# LPC55S69_MINI.net
KiCad netlist of a schematic drawn in Altium Designer
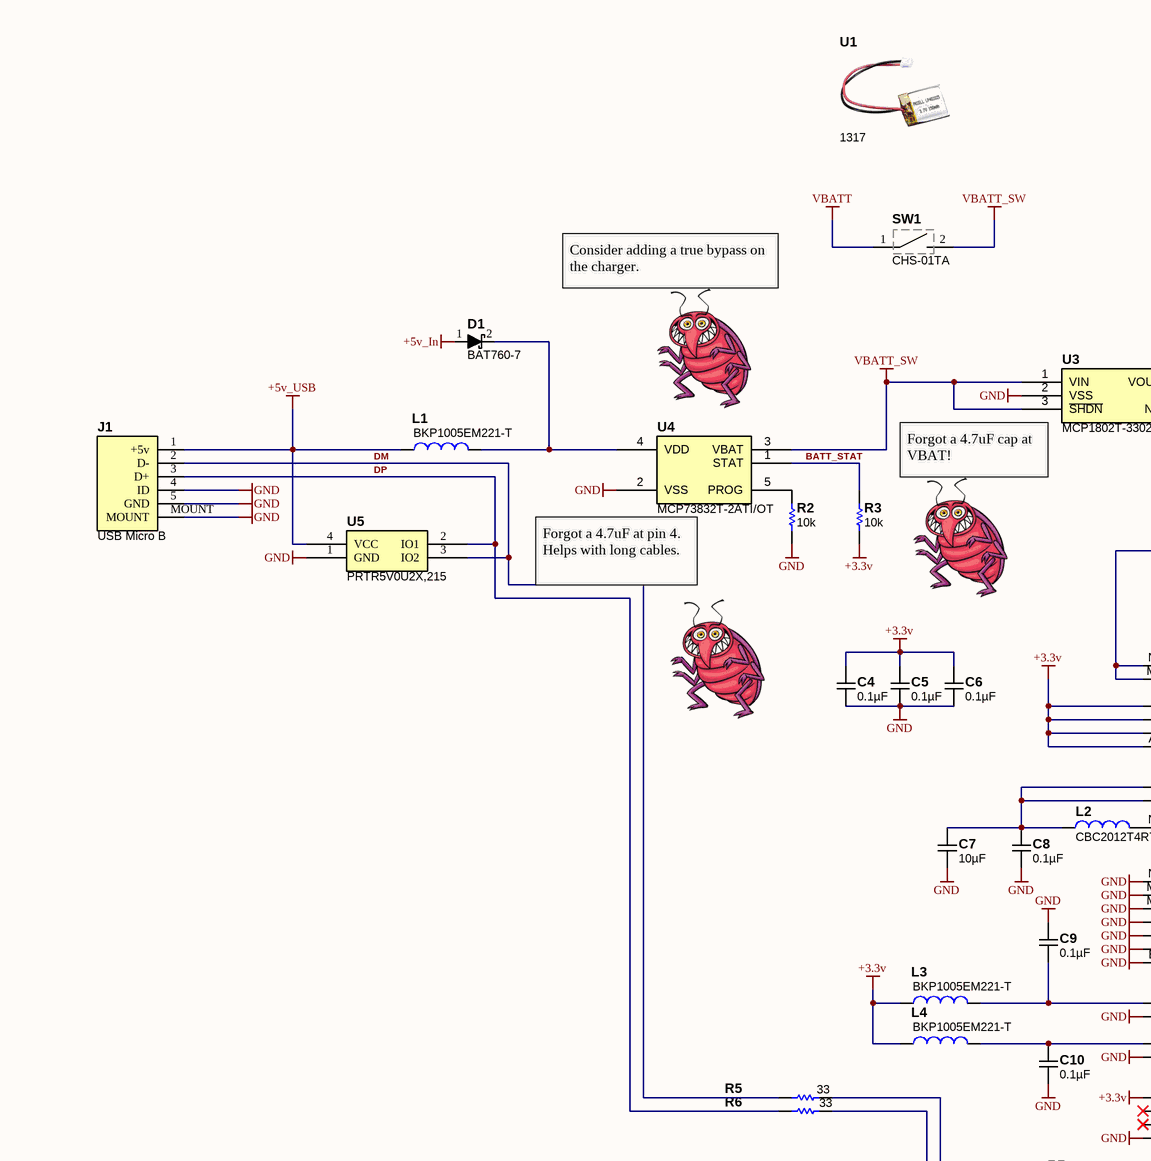
[diagram p0: LPC55S69_MINI.SchDoc, top left]
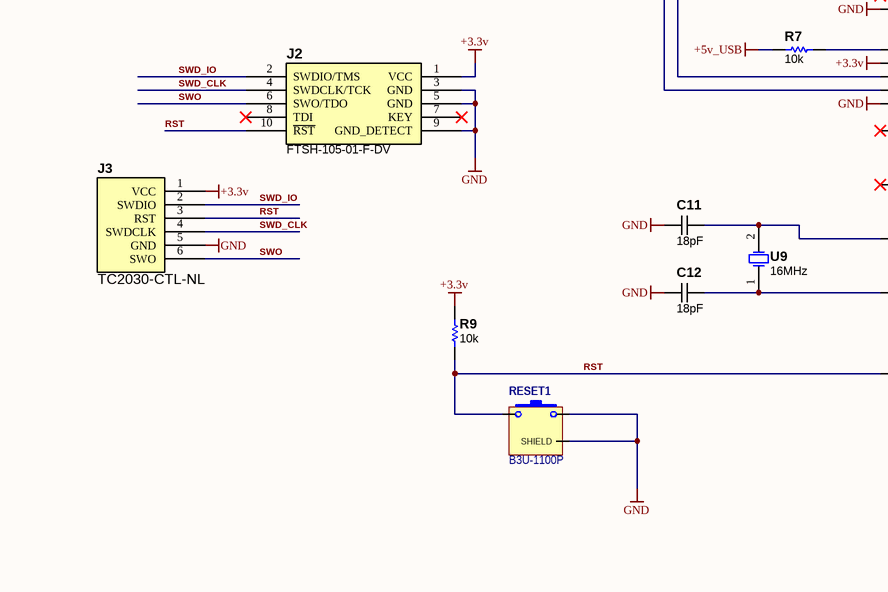
[diagram p1: LPC55S69_MINI.SchDoc, bottom left]
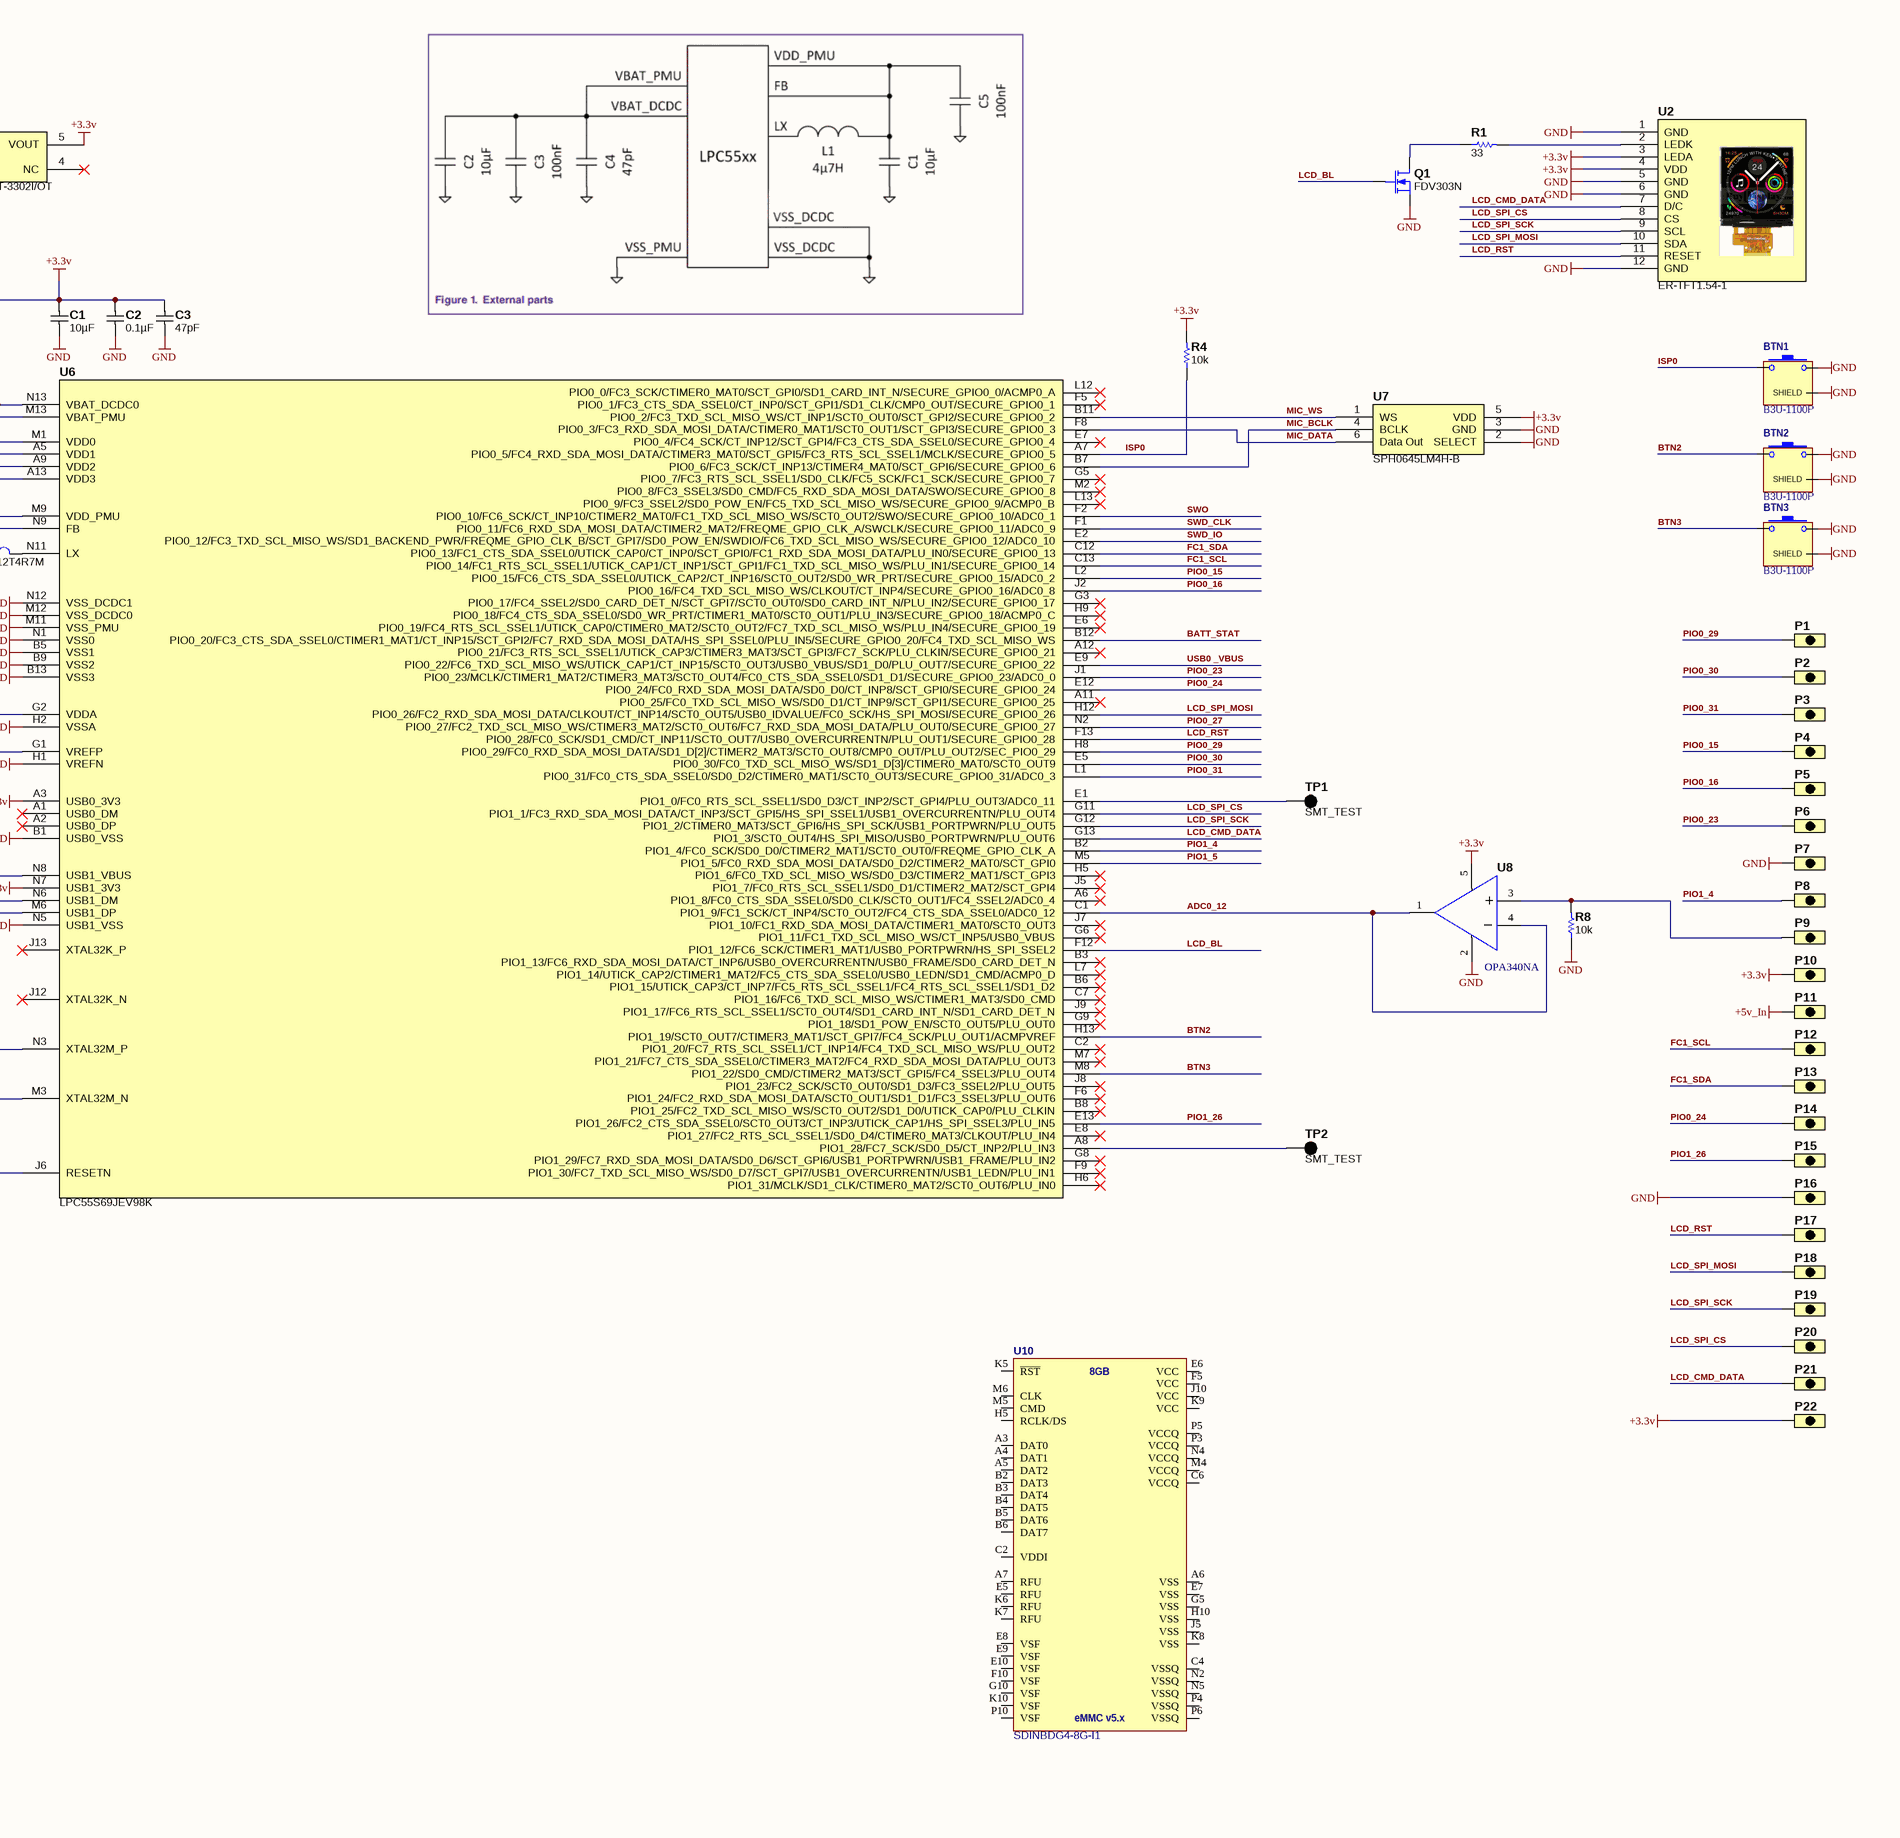
[diagram p2: LPC55S69_MINI.SchDoc, bottom right]

(export (version "E")
  (design (tool "Eeschema 10.0.6"))
  (components
    (comp (ref "BTN1")
      (value "B3U-1100P")
      (footprint "OMRON_B3U-1100P")
      (description "SWITCH TACTILE SPST-NO 0.05A 12V")
      (fields (field (name "MANUFACTURER") "Omron Electronics Inc-EMC Div"))
      (libsource (lib "Switches-N") (part "B3U-1100P"))
    )
    (comp (ref "BTN2")
      (value "B3U-1100P")
      (footprint "OMRON_B3U-1100P")
      (description "SWITCH TACTILE SPST-NO 0.05A 12V")
      (fields (field (name "MANUFACTURER") "Omron Electronics Inc-EMC Div"))
      (libsource (lib "Switches-N") (part "B3U-1100P"))
    )
    (comp (ref "BTN3")
      (value "B3U-1100P")
      (footprint "OMRON_B3U-1100P")
      (description "SWITCH TACTILE SPST-NO 0.05A 12V")
      (fields (field (name "MANUFACTURER") "Omron Electronics Inc-EMC Div"))
      (libsource (lib "Switches-N") (part "B3U-1100P"))
    )
    (comp (ref "C1")
      (value "10µF")
      (footprint "C0805_1.45MM_MD")
      (description "CAP CER 10UF 6.3V X7R 0805")
      (fields
        (field (name "MANUFACTURER PART NUMBER") "CGA4J1X7R0J106K125AC")
        (field (name "MANUFACTURER") "TDK Corporation")
      )
      (libsource (lib "Capacitors - TDK- AEC-Q200") (part "C_2P_NP"))
    )
    (comp (ref "C2")
      (value "0.1µF")
      (footprint "C0402_0.55MM_MD")
      (description "CAP CER 0.1UF 16V X7R 0402")
      (fields
        (field (name "MANUFACTURER PART NUMBER") "CGA2B1X7R1C104K050BC")
        (field (name "MANUFACTURER") "TDK Corporation")
      )
      (libsource (lib "Capacitors - TDK- AEC-Q200") (part "C_2P_NP"))
    )
    (comp (ref "C3")
      (value "47pF")
      (footprint "C0402_0.55MM_MD")
      (description "CAP CER 47PF 50V C0G 0402")
      (fields
        (field (name "MANUFACTURER PART NUMBER") "CGA2B2C0G1H470J050BA")
        (field (name "MANUFACTURER") "TDK Corporation")
      )
      (libsource (lib "Capacitors - TDK- AEC-Q200") (part "C_2P_NP"))
    )
    (comp (ref "C4")
      (value "0.1µF")
      (footprint "C0402_0.55MM_MD")
      (description "CAP CER 0.1UF 16V X7R 0402")
      (fields
        (field (name "MANUFACTURER PART NUMBER") "CGA2B1X7R1C104K050BC")
        (field (name "MANUFACTURER") "TDK Corporation")
      )
      (libsource (lib "Capacitors - TDK- AEC-Q200") (part "C_2P_NP"))
    )
    (comp (ref "C5")
      (value "0.1µF")
      (footprint "C0402_0.55MM_MD")
      (description "CAP CER 0.1UF 16V X7R 0402")
      (fields
        (field (name "MANUFACTURER PART NUMBER") "CGA2B1X7R1C104K050BC")
        (field (name "MANUFACTURER") "TDK Corporation")
      )
      (libsource (lib "Capacitors - TDK- AEC-Q200") (part "C_2P_NP"))
    )
    (comp (ref "C6")
      (value "0.1µF")
      (footprint "C0402_0.55MM_MD")
      (description "CAP CER 0.1UF 16V X7R 0402")
      (fields
        (field (name "MANUFACTURER PART NUMBER") "CGA2B1X7R1C104K050BC")
        (field (name "MANUFACTURER") "TDK Corporation")
      )
      (libsource (lib "Capacitors - TDK- AEC-Q200") (part "C_2P_NP"))
    )
    (comp (ref "C7")
      (value "10µF")
      (footprint "C0805_1.45MM_MD")
      (description "CAP CER 10UF 6.3V X7R 0805")
      (fields
        (field (name "MANUFACTURER PART NUMBER") "CGA4J1X7R0J106K125AC")
        (field (name "MANUFACTURER") "TDK Corporation")
      )
      (libsource (lib "Capacitors - TDK- AEC-Q200") (part "C_2P_NP"))
    )
    (comp (ref "C8")
      (value "0.1µF")
      (footprint "C0402_0.55MM_MD")
      (description "CAP CER 0.1UF 16V X7R 0402")
      (fields
        (field (name "MANUFACTURER PART NUMBER") "CGA2B1X7R1C104K050BC")
        (field (name "MANUFACTURER") "TDK Corporation")
      )
      (libsource (lib "Capacitors - TDK- AEC-Q200") (part "C_2P_NP"))
    )
    (comp (ref "C9")
      (value "0.1µF")
      (footprint "C0402_0.55MM_MD")
      (description "CAP CER 0.1UF 16V X7R 0402")
      (fields
        (field (name "MANUFACTURER PART NUMBER") "CGA2B1X7R1C104K050BC")
        (field (name "MANUFACTURER") "TDK Corporation")
      )
      (libsource (lib "Capacitors - TDK- AEC-Q200") (part "C_2P_NP"))
    )
    (comp (ref "C10")
      (value "0.1µF")
      (footprint "C0402_0.55MM_MD")
      (description "CAP CER 0.1UF 16V X7R 0402")
      (fields
        (field (name "MANUFACTURER PART NUMBER") "CGA2B1X7R1C104K050BC")
        (field (name "MANUFACTURER") "TDK Corporation")
      )
      (libsource (lib "Capacitors - TDK- AEC-Q200") (part "C_2P_NP"))
    )
    (comp (ref "C11")
      (value "18pF")
      (footprint "C0402_0.55MM_MD")
      (description "CAP CER 18PF 50V C0G 0402")
      (fields
        (field (name "MANUFACTURER PART NUMBER") "CGA2B2C0G1H180J050BA")
        (field (name "MANUFACTURER") "TDK Corporation")
      )
      (libsource (lib "Capacitors - TDK- AEC-Q200") (part "C_2P_NP"))
    )
    (comp (ref "C12")
      (value "18pF")
      (footprint "C0402_0.55MM_MD")
      (description "CAP CER 18PF 50V C0G 0402")
      (fields
        (field (name "MANUFACTURER PART NUMBER") "CGA2B2C0G1H180J050BA")
        (field (name "MANUFACTURER") "TDK Corporation")
      )
      (libsource (lib "Capacitors - TDK- AEC-Q200") (part "C_2P_NP"))
    )
    (comp (ref "D1")
      (value "BAT760-7")
      (footprint "D_SOD-323_P")
      (description "DIODE SCHOTTKY 30V 1A SOD323")
      (fields (field (name "MANUFACTURER") "Diodes Inc"))
      (libsource (lib "Diodes") (part "DS_1A_2C"))
    )
    (comp (ref "J1")
      (value "USB Micro B")
      (footprint "10103594-0001LF - No Slots")
      (description "CONN RCPT STD MICRO USB TYPE B")
      (fields (field (name "MANUFACTURER") "FCI") (field (name "MANUFACTURER PART NUMBER") "10103594-0001LF"))
      (libsource (lib "eConnector_USB") (part "10103594-0001LF"))
    )
    (comp (ref "J2")
      (value "FTSH-105-01-F-DV")
      (footprint "FTSH-105-01-F-DV-K-A")
      (description "SAMTEC - FTSH-105-01-F-DV - .050 X .050")
      (fields (field (name "MANUFACTURER") "SAMTEC"))
      (libsource (lib "eConnector") (part "CORTEX-DEBUG"))
    )
    (comp (ref "J3")
      (value "TC2030‐CTL‐NL")
      (footprint "TC2030 NO LATCH")
      (description "Tag Connect Pads - No latching Clips - ARM")
      (libsource (lib "eConnector") (part "TC2030‐CTL‐NL"))
    )
    (comp (ref "L1")
      (value "BKP1005EM221-T")
      (footprint "C0402_HD")
      (description "FERRITE BEAD 220 OHM 0402 1LN")
      (fields (field (name "MANUFACTURER") "Taiyo Yuden"))
      (libsource (lib "eInductor") (part "BKP1005EM221-T"))
    )
    (comp (ref "L2")
      (value "CBC2012T4R7M")
      (footprint "C0805_1.45MM_MD")
      (description "FIXED IND 4.7UH 520MA 650 MOHM")
      (fields (field (name "MANUFACTURER") "Taiyo Yuden") (field (name "TOLERANCE") "20%"))
      (libsource (lib "eInductor") (part "CBC2012T4R7M"))
    )
    (comp (ref "L3")
      (value "BKP1005EM221-T")
      (footprint "C0402_HD")
      (description "FERRITE BEAD 220 OHM 0402 1LN")
      (fields (field (name "MANUFACTURER") "Taiyo Yuden"))
      (libsource (lib "eInductor") (part "BKP1005EM221-T"))
    )
    (comp (ref "L4")
      (value "BKP1005EM221-T")
      (footprint "C0402_HD")
      (description "FERRITE BEAD 220 OHM 0402 1LN")
      (fields (field (name "MANUFACTURER") "Taiyo Yuden"))
      (libsource (lib "eInductor") (part "BKP1005EM221-T"))
    )
    (comp (ref "P1")
      (value "~")
      (footprint "CASTELLATED")
      (libsource (lib "eConnector") (part "CASTELLATED"))
    )
    (comp (ref "P2")
      (value "~")
      (footprint "CASTELLATED")
      (libsource (lib "eConnector") (part "CASTELLATED"))
    )
    (comp (ref "P3")
      (value "~")
      (footprint "CASTELLATED")
      (libsource (lib "eConnector") (part "CASTELLATED"))
    )
    (comp (ref "P4")
      (value "~")
      (footprint "CASTELLATED")
      (libsource (lib "eConnector") (part "CASTELLATED"))
    )
    (comp (ref "P5")
      (value "~")
      (footprint "CASTELLATED")
      (libsource (lib "eConnector") (part "CASTELLATED"))
    )
    (comp (ref "P6")
      (value "~")
      (footprint "CASTELLATED")
      (libsource (lib "eConnector") (part "CASTELLATED"))
    )
    (comp (ref "P7")
      (value "~")
      (footprint "CASTELLATED")
      (libsource (lib "eConnector") (part "CASTELLATED"))
    )
    (comp (ref "P8")
      (value "~")
      (footprint "CASTELLATED")
      (libsource (lib "eConnector") (part "CASTELLATED"))
    )
    (comp (ref "P9")
      (value "~")
      (footprint "CASTELLATED")
      (libsource (lib "eConnector") (part "CASTELLATED"))
    )
    (comp (ref "P10")
      (value "~")
      (footprint "CASTELLATED")
      (libsource (lib "eConnector") (part "CASTELLATED"))
    )
    (comp (ref "P11")
      (value "~")
      (footprint "CASTELLATED")
      (libsource (lib "eConnector") (part "CASTELLATED"))
    )
    (comp (ref "P12")
      (value "~")
      (footprint "CASTELLATED")
      (libsource (lib "eConnector") (part "CASTELLATED"))
    )
    (comp (ref "P13")
      (value "~")
      (footprint "CASTELLATED")
      (libsource (lib "eConnector") (part "CASTELLATED"))
    )
    (comp (ref "P14")
      (value "~")
      (footprint "CASTELLATED")
      (libsource (lib "eConnector") (part "CASTELLATED"))
    )
    (comp (ref "P15")
      (value "~")
      (footprint "CASTELLATED")
      (libsource (lib "eConnector") (part "CASTELLATED"))
    )
    (comp (ref "P16")
      (value "~")
      (footprint "CASTELLATED")
      (libsource (lib "eConnector") (part "CASTELLATED"))
    )
    (comp (ref "P17")
      (value "~")
      (footprint "CASTELLATED")
      (libsource (lib "eConnector") (part "CASTELLATED"))
    )
    (comp (ref "P18")
      (value "~")
      (footprint "CASTELLATED")
      (libsource (lib "eConnector") (part "CASTELLATED"))
    )
    (comp (ref "P19")
      (value "~")
      (footprint "CASTELLATED")
      (libsource (lib "eConnector") (part "CASTELLATED"))
    )
    (comp (ref "P20")
      (value "~")
      (footprint "CASTELLATED")
      (libsource (lib "eConnector") (part "CASTELLATED"))
    )
    (comp (ref "P21")
      (value "~")
      (footprint "CASTELLATED")
      (libsource (lib "eConnector") (part "CASTELLATED"))
    )
    (comp (ref "P22")
      (value "~")
      (footprint "CASTELLATED")
      (libsource (lib "eConnector") (part "CASTELLATED"))
    )
    (comp (ref "Q1")
      (value "FDV303N")
      (footprint "SOT-23")
      (description "MOSFET N-CH 25V 680MA SOT-23")
      (fields (field (name "MANUFACTURER") "Fairchild Semiconductor") (field (name "SOURCE") "Digikey"))
      (libsource (lib "eTransistor") (part "FDV303N"))
    )
    (comp (ref "R1")
      (value "33")
      (footprint "R0603_0.55MM_MD")
      (description "RES 33 OHM 1/10W 1% 0603 SMD")
      (fields
        (field (name "MANUFACTURER PART NUMBER") "ERJ-3EKF33R0V")
        (field (name "MANUFACTURER") "Panasonic Electronic Components")
      )
      (libsource (lib "Resistors - Panasonic - AEC-Q200") (part "R_2P"))
    )
    (comp (ref "R2")
      (value "10k")
      (footprint "R0402_0.40MM_MD")
      (description "RES 10K OHM 1/10W 1% 0402 SMD")
      (fields
        (field (name "MANUFACTURER PART NUMBER") "ERJ-2RKF1002X")
        (field (name "MANUFACTURER") "Panasonic Electronic Components")
      )
      (libsource (lib "Resistors - Panasonic - AEC-Q200") (part "R_2P"))
    )
    (comp (ref "R3")
      (value "10k")
      (footprint "R0402_0.40MM_MD")
      (description "RES 10K OHM 1/10W 1% 0402 SMD")
      (fields
        (field (name "MANUFACTURER PART NUMBER") "ERJ-2RKF1002X")
        (field (name "MANUFACTURER") "Panasonic Electronic Components")
      )
      (libsource (lib "Resistors - Panasonic - AEC-Q200") (part "R_2P"))
    )
    (comp (ref "R4")
      (value "10k")
      (footprint "R0402_0.40MM_MD")
      (description "RES 10K OHM 1/10W 1% 0402 SMD")
      (fields
        (field (name "MANUFACTURER PART NUMBER") "ERJ-2RKF1002X")
        (field (name "MANUFACTURER") "Panasonic Electronic Components")
      )
      (libsource (lib "Resistors - Panasonic - AEC-Q200") (part "R_2P"))
    )
    (comp (ref "R5")
      (value "33")
      (footprint "R0603_0.55MM_MD")
      (description "RES 33 OHM 1/10W 1% 0603 SMD")
      (fields
        (field (name "MANUFACTURER PART NUMBER") "ERJ-3EKF33R0V")
        (field (name "MANUFACTURER") "Panasonic Electronic Components")
      )
      (libsource (lib "Resistors - Panasonic - AEC-Q200") (part "R_2P"))
    )
    (comp (ref "R6")
      (value "33")
      (footprint "R0603_0.55MM_MD")
      (description "RES 33 OHM 1/10W 1% 0603 SMD")
      (fields
        (field (name "MANUFACTURER PART NUMBER") "ERJ-3EKF33R0V")
        (field (name "MANUFACTURER") "Panasonic Electronic Components")
      )
      (libsource (lib "Resistors - Panasonic - AEC-Q200") (part "R_2P"))
    )
    (comp (ref "R7")
      (value "10k")
      (footprint "R0402_0.40MM_MD")
      (description "RES 10K OHM 1/10W 1% 0402 SMD")
      (fields
        (field (name "MANUFACTURER PART NUMBER") "ERJ-2RKF1002X")
        (field (name "MANUFACTURER") "Panasonic Electronic Components")
      )
      (libsource (lib "Resistors - Panasonic - AEC-Q200") (part "R_2P"))
    )
    (comp (ref "R8")
      (value "10k")
      (footprint "R0402_0.40MM_MD")
      (description "RES 10K OHM 1/10W 1% 0402 SMD")
      (fields
        (field (name "MANUFACTURER PART NUMBER") "ERJ-2RKF1002X")
        (field (name "MANUFACTURER") "Panasonic Electronic Components")
      )
      (libsource (lib "Resistors - Panasonic - AEC-Q200") (part "R_2P"))
    )
    (comp (ref "R9")
      (value "10k")
      (footprint "R0402_0.40MM_MD")
      (description "RES 10K OHM 1/10W 1% 0402 SMD")
      (fields
        (field (name "MANUFACTURER PART NUMBER") "ERJ-2RKF1002X")
        (field (name "MANUFACTURER") "Panasonic Electronic Components")
      )
      (libsource (lib "Resistors - Panasonic - AEC-Q200") (part "R_2P"))
    )
    (comp (ref "RESET1")
      (value "B3U-1100P")
      (footprint "OMRON_B3U-1100P")
      (description "SWITCH TACTILE SPST-NO 0.05A 12V")
      (fields (field (name "MANUFACTURER") "Omron Electronics Inc-EMC Div"))
      (libsource (lib "Switches-N") (part "B3U-1100P"))
    )
    (comp (ref "SW1")
      (value "CHS-01TA")
      (footprint "CHS-01TA")
      (description "NIDEC COPAL ELECTRONICS - CHS-01TA - DIP SWITCH, 1POS, SPST, SLIDE, SMD")
      (fields (field (name "MANUFACTURER") "Nidec Copal"))
      (libsource (lib "eElectroMechanical") (part "CHS-01TA"))
    )
    (comp (ref "TP1")
      (value "SMT_TEST")
      (footprint "SMT_TP - 25")
      (libsource (lib "eTestPoint") (part "SMT_TEST"))
    )
    (comp (ref "TP2")
      (value "SMT_TEST")
      (footprint "SMT_TP - 25")
      (libsource (lib "eTestPoint") (part "SMT_TEST"))
    )
    (comp (ref "U1")
      (value "1317")
      (footprint "LIPO-150MAH")
      (description "FLORA LI-PO BATTERY 3.7V 150MAH")
      (fields (field (name "MANUFACTURER") "Adafruit Industries"))
      (libsource (lib "eBattery") (part "1317"))
    )
    (comp (ref "U2")
      (value "ER-TFT1.54-1")
      (footprint "ER-TFT1.54-1")
      (description "1.54\" 240x240 IPS Display")
      (fields (field (name "MANUFACTURER") "Buy Display"))
      (libsource (lib "eDisplay") (part "ER-TFT1.54-1"))
    )
    (comp (ref "U3")
      (value "MCP1802T-3302I/OT")
      (footprint "SOT23-5")
      (description "IC REG LINEAR 3.3V 300MA SOT23-5")
      (fields (field (name "MANUFACTURER") "Microchip"))
      (libsource (lib "eIC_Regulator") (part "MCP1802T-3302I/OT"))
    )
    (comp (ref "U4")
      (value "MCP73832T-2ATI/OT")
      (footprint "SOT23-5")
      (description "Charge Controller Li-Ion/Li-Pol 15mA to 500mA 4.2V 5-Pin SOT-23 T/R")
      (fields (field (name "MANUFACTURER") "Microchip"))
      (libsource (lib "eIC") (part "MCP73832T-2ATI/OT"))
    )
    (comp (ref "U5")
      (value "PRTR5V0U2X,215")
      (footprint "SOT143B")
      (description "TVS DIODE 5.5VWM SOT143B")
      (fields (field (name "MANUFACTURER") "NXP Semiconductors"))
      (libsource (lib "eDiode") (part "PRTR5V0U2X,215"))
    )
    (comp (ref "U6")
      (value "LPC55S69JEV98K")
      (footprint "98-VFBGA")
      (description "IC MCU 100MHZ CORTEX M33 DUAL")
      (fields (field (name "MANUFACTURER") "NXP Semiconductors"))
      (libsource (lib "eIC") (part "LPC55S69JEV98K"))
    )
    (comp (ref "U7")
      (value "SPH0645LM4H-B")
      (footprint "SPH0645LM4H-B")
      (fields (field (name "MANUFACTURER") "Knowles Acoustics"))
      (libsource (lib "eAudio") (part "SPH0645LM4H-B"))
    )
    (comp (ref "U8")
      (value "OPA340NA")
      (footprint "SOT95P245X145-5L")
      (description "IC SINGLE SUPPLY OPAMP SOT-23-5")
      (fields
        (field (name "MANUFACTURER") "Texas Instruments")
        (field (name "MANUFACTURER PART NUMBER") "OPA340NA/250")
        (field (name "SOURCE") "Digikey")
      )
      (libsource (lib "eOPAMP") (part "OPA340"))
    )
    (comp (ref "U9")
      (value "16MHz")
      (footprint "ABM3")
      (description "Crystal 16MHz ±20ppm (Tol) ±50ppm (Stability) 18pF FUND 50Ohm 2-Pin CSMD T/R")
      (fields
        (field (name "MANUFACTURER") "Abracon")
        (field (name "MANUFACTURER PART NUMBER") "ABM3-16.000MHZ-B2-T")
      )
      (libsource (lib "eCrystal") (part "ABM3-16.000MHZ-B2-T"))
    )
    (comp (ref "U10")
      (value "SDINBDG4-8G-I1")
      (footprint "BGA_JDEC_EMMC_11.5x13.1x1.1_153PIN")
      (description "eMMC eMMC seq 300/40 IOPs 7800/8000")
      (fields (field (name "MANUFACTURER") "SanDisk"))
      (libsource (lib "Memory-N") (part "SDINBDG4-8G-I1"))
    )
  )
  (nets
    (net (code "1") (name "+3.3v") (class "Default")
      (node (ref "C1") (pin "2") (pinfunction "1_2") (pintype "passive"))
      (node (ref "C2") (pin "2") (pinfunction "1_2") (pintype "passive"))
      (node (ref "C3") (pin "2") (pinfunction "1_2") (pintype "passive"))
      (node (ref "C4") (pin "2") (pinfunction "1_2") (pintype "passive"))
      (node (ref "C5") (pin "2") (pinfunction "1_2") (pintype "passive"))
      (node (ref "C6") (pin "2") (pinfunction "1_2") (pintype "passive"))
      (node (ref "J2") (pin "1") (pinfunction "VCC_1") (pintype "passive"))
      (node (ref "J3") (pin "1") (pinfunction "VCC_1") (pintype "passive"))
      (node (ref "L3") (pin "1") (pinfunction "1_1") (pintype "passive"))
      (node (ref "L4") (pin "1") (pinfunction "1_1") (pintype "passive"))
      (node (ref "P10") (pin "1") (pinfunction "1_1") (pintype "passive"))
      (node (ref "P22") (pin "1") (pinfunction "1_1") (pintype "passive"))
      (node (ref "R3") (pin "1") (pinfunction "1_1") (pintype "passive"))
      (node (ref "R4") (pin "2") (pinfunction "2_2") (pintype "passive"))
      (node (ref "R9") (pin "2") (pinfunction "2_2") (pintype "passive"))
      (node (ref "U2") (pin "3") (pinfunction "LEDA_3") (pintype "passive"))
      (node (ref "U2") (pin "4") (pinfunction "VDD_4") (pintype "passive"))
      (node (ref "U3") (pin "5") (pinfunction "VOUT_5") (pintype "passive"))
      (node (ref "U6") (pin "A13") (pinfunction "VDD3_A13") (pintype "passive"))
      (node (ref "U6") (pin "A3") (pinfunction "USB0_3V3_A3") (pintype "passive"))
      (node (ref "U6") (pin "A5") (pinfunction "VDD1_A5") (pintype "passive"))
      (node (ref "U6") (pin "A9") (pinfunction "VDD2_A9") (pintype "passive"))
      (node (ref "U6") (pin "M1") (pinfunction "VDD0_M1") (pintype "passive"))
      (node (ref "U6") (pin "M13") (pinfunction "VBAT_PMU_M13") (pintype "passive"))
      (node (ref "U6") (pin "N13") (pinfunction "VBAT_DCDC0_N13") (pintype "passive"))
      (node (ref "U6") (pin "N7") (pinfunction "USB1_3V3_N7") (pintype "passive"))
      (node (ref "U7") (pin "5") (pinfunction "VDD_5") (pintype "passive"))
      (node (ref "U8") (pin "5") (pinfunction "VCC_5") (pintype "passive"))
    )
    (net (code "2") (name "+5v_In") (class "Default")
      (node (ref "D1") (pin "1") (pinfunction "A_1") (pintype "passive"))
      (node (ref "P11") (pin "1") (pinfunction "1_1") (pintype "passive"))
    )
    (net (code "3") (name "+5v_USB") (class "Default")
      (node (ref "J1") (pin "1") (pinfunction "+5v_1") (pintype "passive"))
      (node (ref "L1") (pin "1") (pinfunction "1_1") (pintype "passive"))
      (node (ref "R7") (pin "2") (pinfunction "2_2") (pintype "passive"))
      (node (ref "U5") (pin "4") (pinfunction "VCC_4") (pintype "passive"))
    )
    (net (code "4") (name "/ADC0_12") (class "Default")
      (node (ref "U6") (pin "C1") (pinfunction "PIO1_9/FC1_SCK/CT_INP4/SCT0_OUT2/FC4_CTS_SDA_SSEL0/ADC0_12_C1") (pintype "passive"))
      (node (ref "U8") (pin "1") (pinfunction "OUT_1") (pintype "passive"))
      (node (ref "U8") (pin "4") (pinfunction "-_4") (pintype "passive"))
    )
    (net (code "5") (name "/BATT_STAT") (class "Default")
      (node (ref "R3") (pin "2") (pinfunction "2_2") (pintype "passive"))
      (node (ref "U4") (pin "1") (pinfunction "STAT_1") (pintype "passive"))
      (node (ref "U6") (pin "B12") (pinfunction "PIO0_20/FC3_CTS_SDA_SSEL0/CTIMER1_MAT1/CT_INP15/SCT_GPI2/FC7_RXD_SDA_MOSI_DATA/HS_SPI_SSEL0/PLU_IN5/SECURE_GPIO0_20/FC4_TXD_SCL_MISO_WS_B12") (pintype "passive"))
    )
    (net (code "6") (name "/BTN2") (class "Default")
      (node (ref "BTN2") (pin "2") (pinfunction "2_2") (pintype "passive"))
      (node (ref "U6") (pin "H13") (pinfunction "PIO1_19/SCT0_OUT7/CTIMER3_MAT1/SCT_GPI7/FC4_SCK/PLU_OUT1/ACMPVREF_H13") (pintype "passive"))
    )
    (net (code "7") (name "/BTN3") (class "Default")
      (node (ref "BTN3") (pin "2") (pinfunction "2_2") (pintype "passive"))
      (node (ref "U6") (pin "M8") (pinfunction "PIO1_22/SD0_CMD/CTIMER2_MAT3/SCT_GPI5/FC4_SSEL3/PLU_OUT4_M8") (pintype "passive"))
    )
    (net (code "8") (name "/DM") (class "Default")
      (node (ref "J1") (pin "2") (pinfunction "D-_2") (pintype "passive"))
      (node (ref "R5") (pin "1") (pinfunction "1_1") (pintype "passive"))
      (node (ref "U5") (pin "3") (pinfunction "IO2_3") (pintype "passive"))
    )
    (net (code "9") (name "/DP") (class "Default")
      (node (ref "J1") (pin "3") (pinfunction "D+_3") (pintype "passive"))
      (node (ref "R6") (pin "1") (pinfunction "1_1") (pintype "passive"))
      (node (ref "U5") (pin "2") (pinfunction "IO1_2") (pintype "passive"))
    )
    (net (code "10") (name "/FC1_SCL") (class "Default")
      (node (ref "P12") (pin "1") (pinfunction "1_1") (pintype "passive"))
      (node (ref "U6") (pin "C13") (pinfunction "PIO0_14/FC1_RTS_SCL_SSEL1/UTICK_CAP1/CT_INP1/SCT_GPI1/FC1_TXD_SCL_MISO_WS/PLU_IN1/SECURE_GPIO0_14_C13") (pintype "passive"))
    )
    (net (code "11") (name "/FC1_SDA") (class "Default")
      (node (ref "P13") (pin "1") (pinfunction "1_1") (pintype "passive"))
      (node (ref "U6") (pin "C12") (pinfunction "PIO0_13/FC1_CTS_SDA_SSEL0/UTICK_CAP0/CT_INP0/SCT_GPI0/FC1_RXD_SDA_MOSI_DATA/PLU_IN0/SECURE_GPIO0_13_C12") (pintype "passive"))
    )
    (net (code "12") (name "/ISP0") (class "Default")
      (node (ref "BTN1") (pin "2") (pinfunction "2_2") (pintype "passive"))
      (node (ref "R4") (pin "1") (pinfunction "1_1") (pintype "passive"))
      (node (ref "U6") (pin "A7") (pinfunction "PIO0_5/FC4_RXD_SDA_MOSI_DATA/CTIMER3_MAT0/SCT_GPI5/FC3_RTS_SCL_SSEL1/MCLK/SECURE_GPIO0_5_A7") (pintype "passive"))
    )
    (net (code "13") (name "/LCD_BL") (class "Default")
      (node (ref "Q1") (pin "1") (pinfunction "G_1") (pintype "passive"))
      (node (ref "U6") (pin "F12") (pinfunction "PIO1_12/FC6_SCK/CTIMER1_MAT1/USB0_PORTPWRN/HS_SPI_SSEL2_F12") (pintype "passive"))
    )
    (net (code "14") (name "/LCD_CMD_DATA") (class "Default")
      (node (ref "P21") (pin "1") (pinfunction "1_1") (pintype "passive"))
      (node (ref "U2") (pin "7") (pinfunction "D/C_7") (pintype "passive"))
      (node (ref "U6") (pin "G13") (pinfunction "PIO1_3/SCT0_OUT4/HS_SPI_MISO/USB0_PORTPWRN/PLU_OUT6_G13") (pintype "passive"))
    )
    (net (code "15") (name "/LCD_RST") (class "Default")
      (node (ref "P17") (pin "1") (pinfunction "1_1") (pintype "passive"))
      (node (ref "U2") (pin "11") (pinfunction "RESET_11") (pintype "passive"))
      (node (ref "U6") (pin "F13") (pinfunction "PIO0_28/FC0_SCK/SD1_CMD/CT_INP11/SCT0_OUT7/USB0_OVERCURRENTN/PLU_OUT1/SECURE_GPIO0_28_F13") (pintype "passive"))
    )
    (net (code "16") (name "/LCD_SPI_CS") (class "Default")
      (node (ref "P20") (pin "1") (pinfunction "1_1") (pintype "passive"))
      (node (ref "U2") (pin "8") (pinfunction "CS_8") (pintype "passive"))
      (node (ref "U6") (pin "G11") (pinfunction "PIO1_1/FC3_RXD_SDA_MOSI_DATA/CT_INP3/SCT_GPI5/HS_SPI_SSEL1/USB1_OVERCURRENTN/PLU_OUT4_G11") (pintype "passive"))
    )
    (net (code "17") (name "/LCD_SPI_MOSI") (class "Default")
      (node (ref "P18") (pin "1") (pinfunction "1_1") (pintype "passive"))
      (node (ref "U2") (pin "10") (pinfunction "SDA_10") (pintype "passive"))
      (node (ref "U6") (pin "H12") (pinfunction "PIO0_26/FC2_RXD_SDA_MOSI_DATA/CLKOUT/CT_INP14/SCT0_OUT5/USB0_IDVALUE/FC0_SCK/HS_SPI_MOSI/SECURE_GPIO0_26_H12") (pintype "passive"))
    )
    (net (code "18") (name "/LCD_SPI_SCK") (class "Default")
      (node (ref "P19") (pin "1") (pinfunction "1_1") (pintype "passive"))
      (node (ref "U2") (pin "9") (pinfunction "SCL_9") (pintype "passive"))
      (node (ref "U6") (pin "G12") (pinfunction "PIO1_2/CTIMER0_MAT3/SCT_GPI6/HS_SPI_SCK/USB1_PORTPWRN/PLU_OUT5_G12") (pintype "passive"))
    )
    (net (code "19") (name "/MIC_BCLK") (class "Default")
      (node (ref "U6") (pin "B7") (pinfunction "PIO0_6/FC3_SCK/CT_INP13/CTIMER4_MAT0/SCT_GPI6/SECURE_GPIO0_6_B7") (pintype "passive"))
      (node (ref "U7") (pin "4") (pinfunction "BCLK_4") (pintype "passive"))
    )
    (net (code "20") (name "/MIC_DATA") (class "Default")
      (node (ref "U6") (pin "F8") (pinfunction "PIO0_3/FC3_RXD_SDA_MOSI_DATA/CTIMER0_MAT1/SCT0_OUT1/SCT_GPI3/SECURE_GPIO0_3_F8") (pintype "passive"))
      (node (ref "U7") (pin "6") (pinfunction "Data_Out_6") (pintype "passive"))
    )
    (net (code "21") (name "/MIC_WS") (class "Default")
      (node (ref "U6") (pin "B11") (pinfunction "PIO0_2/FC3_TXD_SCL_MISO_WS/CT_INP1/SCT0_OUT0/SCT_GPI2/SECURE_GPIO0_2_B11") (pintype "passive"))
      (node (ref "U7") (pin "1") (pinfunction "WS_1") (pintype "passive"))
    )
    (net (code "22") (name "/PIO0_15") (class "Default")
      (node (ref "P4") (pin "1") (pinfunction "1_1") (pintype "passive"))
      (node (ref "U6") (pin "L2") (pinfunction "PIO0_15/FC6_CTS_SDA_SSEL0/UTICK_CAP2/CT_INP16/SCT0_OUT2/SD0_WR_PRT/SECURE_GPIO0_15/ADC0_2_L2") (pintype "passive"))
    )
    (net (code "23") (name "/PIO0_16") (class "Default")
      (node (ref "P5") (pin "1") (pinfunction "1_1") (pintype "passive"))
      (node (ref "U6") (pin "J2") (pinfunction "PIO0_16/FC4_TXD_SCL_MISO_WS/CLKOUT/CT_INP4/SECURE_GPIO0_16/ADC0_8_J2") (pintype "passive"))
    )
    (net (code "24") (name "/PIO0_23") (class "Default")
      (node (ref "P6") (pin "1") (pinfunction "1_1") (pintype "passive"))
      (node (ref "U6") (pin "J1") (pinfunction "PIO0_23/MCLK/CTIMER1_MAT2/CTIMER3_MAT3/SCT0_OUT4/FC0_CTS_SDA_SSEL0/SD1_D1/SECURE_GPIO0_23/ADC0_0_J1") (pintype "passive"))
    )
    (net (code "25") (name "/PIO0_24") (class "Default")
      (node (ref "P14") (pin "1") (pinfunction "1_1") (pintype "passive"))
      (node (ref "U6") (pin "E12") (pinfunction "PIO0_24/FC0_RXD_SDA_MOSI_DATA/SD0_D0/CT_INP8/SCT_GPI0/SECURE_GPIO0_24_E12") (pintype "passive"))
    )
    (net (code "26") (name "/PIO0_27") (class "Default")
      (node (ref "U6") (pin "N2") (pinfunction "PIO0_27/FC2_TXD_SCL_MISO_WS/CTIMER3_MAT2/SCT0_OUT6/FC7_RXD_SDA_MOSI_DATA/PLU_OUT0/SECURE_GPIO0_27_N2") (pintype "passive"))
    )
    (net (code "27") (name "/PIO0_29") (class "Default")
      (node (ref "P1") (pin "1") (pinfunction "1_1") (pintype "passive"))
      (node (ref "U6") (pin "H8") (pinfunction "PIO0_29/FC0_RXD_SDA_MOSI_DATA/SD1_D[2]/CTIMER2_MAT3/SCT0_OUT8/CMP0_OUT/PLU_OUT2/SEC_PIO0_29_H8") (pintype "passive"))
    )
    (net (code "28") (name "/PIO0_30") (class "Default")
      (node (ref "P2") (pin "1") (pinfunction "1_1") (pintype "passive"))
      (node (ref "U6") (pin "E5") (pinfunction "PIO0_30/FC0_TXD_SCL_MISO_WS/SD1_D[3]/CTIMER0_MAT0/SCT0_OUT9_E5") (pintype "passive"))
    )
    (net (code "29") (name "/PIO0_31") (class "Default")
      (node (ref "P3") (pin "1") (pinfunction "1_1") (pintype "passive"))
      (node (ref "U6") (pin "L1") (pinfunction "PIO0_31/FC0_CTS_SDA_SSEL0/SD0_D2/CTIMER0_MAT1/SCT0_OUT3/SECURE_GPIO0_31/ADC0_3_L1") (pintype "passive"))
    )
    (net (code "30") (name "/PIO1_4") (class "Default")
      (node (ref "P8") (pin "1") (pinfunction "1_1") (pintype "passive"))
      (node (ref "U6") (pin "B2") (pinfunction "PIO1_4/FC0_SCK/SD0_D0/CTIMER2_MAT1/SCT0_OUT0/FREQME_GPIO_CLK_A_B2") (pintype "passive"))
    )
    (net (code "31") (name "/PIO1_5") (class "Default")
      (node (ref "U6") (pin "M5") (pinfunction "PIO1_5/FC0_RXD_SDA_MOSI_DATA/SD0_D2/CTIMER2_MAT0/SCT_GPI0_M5") (pintype "passive"))
    )
    (net (code "32") (name "/PIO1_26") (class "Default")
      (node (ref "P15") (pin "1") (pinfunction "1_1") (pintype "passive"))
      (node (ref "U6") (pin "E13") (pinfunction "PIO1_26/FC2_CTS_SDA_SSEL0/SCT0_OUT3/CT_INP3/UTICK_CAP1/HS_SPI_SSEL3/PLU_IN5_E13") (pintype "passive"))
    )
    (net (code "33") (name "/RST") (class "Default")
      (node (ref "J2") (pin "10") (pinfunction "~{RST}_10") (pintype "passive"))
      (node (ref "J3") (pin "3") (pinfunction "RST_3") (pintype "passive"))
      (node (ref "R9") (pin "1") (pinfunction "1_1") (pintype "passive"))
      (node (ref "RESET1") (pin "2") (pinfunction "2_2") (pintype "passive"))
      (node (ref "U6") (pin "J6") (pinfunction "RESETN_J6") (pintype "passive"))
    )
    (net (code "34") (name "/SWD_CLK") (class "Default")
      (node (ref "J2") (pin "4") (pinfunction "SWDCLK/TCK_4") (pintype "passive"))
      (node (ref "J3") (pin "4") (pinfunction "SWDCLK_4") (pintype "passive"))
      (node (ref "U6") (pin "F1") (pinfunction "PIO0_11/FC6_RXD_SDA_MOSI_DATA/CTIMER2_MAT2/FREQME_GPIO_CLK_A/SWCLK/SECURE_GPIO0_11/ADC0_9_F1") (pintype "passive"))
    )
    (net (code "35") (name "/SWD_IO") (class "Default")
      (node (ref "J2") (pin "2") (pinfunction "SWDIO/TMS_2") (pintype "passive"))
      (node (ref "J3") (pin "2") (pinfunction "SWDIO_2") (pintype "passive"))
      (node (ref "U6") (pin "E2") (pinfunction "PIO0_12/FC3_TXD_SCL_MISO_WS/SD1_BACKEND_PWR/FREQME_GPIO_CLK_B/SCT_GPI7/SD0_POW_EN/SWDIO/FC6_TXD_SCL_MISO_WS/SECURE_GPIO0_12/ADC0_10_E2") (pintype "passive"))
    )
    (net (code "36") (name "/SWO") (class "Default")
      (node (ref "J2") (pin "6") (pinfunction "SWO/TDO_6") (pintype "passive"))
      (node (ref "J3") (pin "6") (pinfunction "SWO_6") (pintype "passive"))
      (node (ref "U6") (pin "F2") (pinfunction "PIO0_10/FC6_SCK/CT_INP10/CTIMER2_MAT0/FC1_TXD_SCL_MISO_WS/SCT0_OUT2/SWO/SECURE_GPIO0_10/ADC0_1_F2") (pintype "passive"))
    )
    (net (code "37") (name "/USB0 _VBUS") (class "Default")
      (node (ref "U6") (pin "E9") (pinfunction "PIO0_22/FC6_TXD_SCL_MISO_WS/UTICK_CAP1/CT_INP15/SCT0_OUT3/USB0_VBUS/SD1_D0/PLU_OUT7/SECURE_GPIO0_22_E9") (pintype "passive"))
    )
    (net (code "38") (name "GND") (class "Default")
      (node (ref "BTN1") (pin "1") (pinfunction "1_1") (pintype "passive"))
      (node (ref "BTN1") (pin "S") (pinfunction "SHIELD_S") (pintype "passive"))
      (node (ref "BTN2") (pin "1") (pinfunction "1_1") (pintype "passive"))
      (node (ref "BTN2") (pin "S") (pinfunction "SHIELD_S") (pintype "passive"))
      (node (ref "BTN3") (pin "1") (pinfunction "1_1") (pintype "passive"))
      (node (ref "BTN3") (pin "S") (pinfunction "SHIELD_S") (pintype "passive"))
      (node (ref "C1") (pin "1") (pinfunction "1_1") (pintype "passive"))
      (node (ref "C10") (pin "1") (pinfunction "1_1") (pintype "passive"))
      (node (ref "C11") (pin "1") (pinfunction "1_1") (pintype "passive"))
      (node (ref "C12") (pin "1") (pinfunction "1_1") (pintype "passive"))
      (node (ref "C2") (pin "1") (pinfunction "1_1") (pintype "passive"))
      (node (ref "C3") (pin "1") (pinfunction "1_1") (pintype "passive"))
      (node (ref "C4") (pin "1") (pinfunction "1_1") (pintype "passive"))
      (node (ref "C5") (pin "1") (pinfunction "1_1") (pintype "passive"))
      (node (ref "C6") (pin "1") (pinfunction "1_1") (pintype "passive"))
      (node (ref "C7") (pin "1") (pinfunction "1_1") (pintype "passive"))
      (node (ref "C8") (pin "1") (pinfunction "1_1") (pintype "passive"))
      (node (ref "C9") (pin "2") (pinfunction "1_2") (pintype "passive"))
      (node (ref "J1") (pin "4") (pinfunction "ID_4") (pintype "passive"))
      (node (ref "J1") (pin "5") (pinfunction "GND_5") (pintype "passive"))
      (node (ref "J1") (pin "MOUNT") (pinfunction "MOUNT_MOUNT") (pintype "passive"))
      (node (ref "J2") (pin "3") (pinfunction "GND_3") (pintype "passive"))
      (node (ref "J2") (pin "5") (pinfunction "GND_5") (pintype "passive"))
      (node (ref "J2") (pin "9") (pinfunction "GND_DETECT_9") (pintype "passive"))
      (node (ref "J3") (pin "5") (pinfunction "GND_5") (pintype "passive"))
      (node (ref "P16") (pin "1") (pinfunction "1_1") (pintype "passive"))
      (node (ref "P7") (pin "1") (pinfunction "1_1") (pintype "passive"))
      (node (ref "Q1") (pin "2") (pinfunction "S_2") (pintype "passive"))
      (node (ref "R2") (pin "1") (pinfunction "1_1") (pintype "passive"))
      (node (ref "R8") (pin "1") (pinfunction "1_1") (pintype "passive"))
      (node (ref "RESET1") (pin "1") (pinfunction "1_1") (pintype "passive"))
      (node (ref "RESET1") (pin "S") (pinfunction "SHIELD_S") (pintype "passive"))
      (node (ref "U2") (pin "1") (pinfunction "GND_1") (pintype "passive"))
      (node (ref "U2") (pin "12") (pinfunction "GND_12") (pintype "passive"))
      (node (ref "U2") (pin "5") (pinfunction "GND_5") (pintype "passive"))
      (node (ref "U2") (pin "6") (pinfunction "GND_6") (pintype "passive"))
      (node (ref "U3") (pin "2") (pinfunction "VSS_2") (pintype "passive"))
      (node (ref "U4") (pin "2") (pinfunction "VSS_2") (pintype "passive"))
      (node (ref "U5") (pin "1") (pinfunction "GND_1") (pintype "passive"))
      (node (ref "U6") (pin "B1") (pinfunction "USB0_VSS_B1") (pintype "passive"))
      (node (ref "U6") (pin "B13") (pinfunction "VSS3_B13") (pintype "passive"))
      (node (ref "U6") (pin "B5") (pinfunction "VSS1_B5") (pintype "passive"))
      (node (ref "U6") (pin "B9") (pinfunction "VSS2_B9") (pintype "passive"))
      (node (ref "U6") (pin "H1") (pinfunction "VREFN_H1") (pintype "passive"))
      (node (ref "U6") (pin "H2") (pinfunction "VSSA_H2") (pintype "passive"))
      (node (ref "U6") (pin "M11") (pinfunction "VSS_PMU_M11") (pintype "passive"))
      (node (ref "U6") (pin "M12") (pinfunction "VSS_DCDC0_M12") (pintype "passive"))
      (node (ref "U6") (pin "N1") (pinfunction "VSS0_N1") (pintype "passive"))
      (node (ref "U6") (pin "N12") (pinfunction "VSS_DCDC1_N12") (pintype "passive"))
      (node (ref "U6") (pin "N5") (pinfunction "USB1_VSS_N5") (pintype "passive"))
      (node (ref "U7") (pin "2") (pinfunction "SELECT_2") (pintype "passive"))
      (node (ref "U7") (pin "3") (pinfunction "GND_3") (pintype "passive"))
      (node (ref "U8") (pin "2") (pinfunction "GND_2") (pintype "passive"))
    )
    (net (code "39") (name "Net-(D1-K)") (class "Default")
      (node (ref "D1") (pin "2") (pinfunction "K_2") (pintype "passive"))
      (node (ref "L1") (pin "2") (pinfunction "2_2") (pintype "passive"))
      (node (ref "U4") (pin "4") (pinfunction "VDD_4") (pintype "passive"))
    )
    (net (code "40") (name "Net-(Q1-D)") (class "Default")
      (node (ref "Q1") (pin "3") (pinfunction "D_3") (pintype "passive"))
      (node (ref "R1") (pin "1") (pinfunction "1_1") (pintype "passive"))
    )
    (net (code "41") (name "Net-(U2-LEDK)") (class "Default")
      (node (ref "R1") (pin "2") (pinfunction "2_2") (pintype "passive"))
      (node (ref "U2") (pin "2") (pinfunction "LEDK_2") (pintype "passive"))
    )
    (net (code "42") (name "Net-(U4-PROG)") (class "Default")
      (node (ref "R2") (pin "2") (pinfunction "2_2") (pintype "passive"))
      (node (ref "U4") (pin "5") (pinfunction "PROG_5") (pintype "passive"))
    )
    (net (code "43") (name "Net-(U6-FB)") (class "Default")
      (node (ref "C7") (pin "2") (pinfunction "1_2") (pintype "passive"))
      (node (ref "C8") (pin "2") (pinfunction "1_2") (pintype "passive"))
      (node (ref "L2") (pin "1") (pinfunction "1_1") (pintype "passive"))
      (node (ref "U6") (pin "M9") (pinfunction "VDD_PMU_M9") (pintype "passive"))
      (node (ref "U6") (pin "N9") (pinfunction "FB_N9") (pintype "passive"))
    )
    (net (code "44") (name "Net-(U6-LX)") (class "Default")
      (node (ref "L2") (pin "2") (pinfunction "2_2") (pintype "passive"))
      (node (ref "U6") (pin "N11") (pinfunction "LX_N11") (pintype "passive"))
    )
    (net (code "45") (name "Net-(U6-PIO1_0{slash}FC0_RTS_SCL_SSEL1{slash}SD0_D3{slash}CT_INP2{slash}SCT_GPI4{slash}PLU_OUT3{slash}ADC0_11)") (class "Default")
      (node (ref "TP1") (pin "1") (pinfunction "1_1") (pintype "passive"))
      (node (ref "U6") (pin "E1") (pinfunction "PIO1_0/FC0_RTS_SCL_SSEL1/SD0_D3/CT_INP2/SCT_GPI4/PLU_OUT3/ADC0_11_E1") (pintype "passive"))
    )
    (net (code "46") (name "Net-(U6-PIO1_28{slash}FC7_SCK{slash}SD0_D5{slash}CT_INP2{slash}PLU_IN3)") (class "Default")
      (node (ref "TP2") (pin "1") (pinfunction "1_1") (pintype "passive"))
      (node (ref "U6") (pin "A8") (pinfunction "PIO1_28/FC7_SCK/SD0_D5/CT_INP2/PLU_IN3_A8") (pintype "passive"))
    )
    (net (code "47") (name "Net-(U6-USB1_DM)") (class "Default")
      (node (ref "R5") (pin "2") (pinfunction "2_2") (pintype "passive"))
      (node (ref "U6") (pin "N6") (pinfunction "USB1_DM_N6") (pintype "passive"))
    )
    (net (code "48") (name "Net-(U6-USB1_DP)") (class "Default")
      (node (ref "R6") (pin "2") (pinfunction "2_2") (pintype "passive"))
      (node (ref "U6") (pin "M6") (pinfunction "USB1_DP_M6") (pintype "passive"))
    )
    (net (code "49") (name "Net-(U6-USB1_VBUS)") (class "Default")
      (node (ref "R7") (pin "1") (pinfunction "1_1") (pintype "passive"))
      (node (ref "U6") (pin "N8") (pinfunction "USB1_VBUS_N8") (pintype "passive"))
    )
    (net (code "50") (name "Net-(U6-VDDA)") (class "Default")
      (node (ref "C9") (pin "1") (pinfunction "1_1") (pintype "passive"))
      (node (ref "L3") (pin "2") (pinfunction "2_2") (pintype "passive"))
      (node (ref "U6") (pin "G2") (pinfunction "VDDA_G2") (pintype "passive"))
    )
    (net (code "51") (name "Net-(U6-VREFP)") (class "Default")
      (node (ref "C10") (pin "2") (pinfunction "1_2") (pintype "passive"))
      (node (ref "L4") (pin "2") (pinfunction "2_2") (pintype "passive"))
      (node (ref "U6") (pin "G1") (pinfunction "VREFP_G1") (pintype "passive"))
    )
    (net (code "52") (name "Net-(U6-XTAL32M_N)") (class "Default")
      (node (ref "C12") (pin "2") (pinfunction "1_2") (pintype "passive"))
      (node (ref "U6") (pin "M3") (pinfunction "XTAL32M_N_M3") (pintype "passive"))
      (node (ref "U9") (pin "1") (pinfunction "OSC1_1") (pintype "passive"))
    )
    (net (code "53") (name "Net-(U6-XTAL32M_P)") (class "Default")
      (node (ref "C11") (pin "2") (pinfunction "1_2") (pintype "passive"))
      (node (ref "U6") (pin "N3") (pinfunction "XTAL32M_P_N3") (pintype "passive"))
      (node (ref "U9") (pin "2") (pinfunction "OSC2_2") (pintype "passive"))
    )
    (net (code "54") (name "Net-(U8-+)") (class "Default")
      (node (ref "P9") (pin "1") (pinfunction "1_1") (pintype "passive"))
      (node (ref "R8") (pin "2") (pinfunction "2_2") (pintype "passive"))
      (node (ref "U8") (pin "3") (pinfunction "+_3") (pintype "passive"))
    )
    (net (code "55") (name "VBATT") (class "Default")
      (node (ref "SW1") (pin "1") (pinfunction "1_1") (pintype "passive"))
    )
    (net (code "56") (name "VBATT_SW") (class "Default")
      (node (ref "SW1") (pin "2") (pinfunction "2_2") (pintype "passive"))
      (node (ref "U3") (pin "1") (pinfunction "VIN_1") (pintype "passive"))
      (node (ref "U3") (pin "3") (pinfunction "~{SHDN}_3") (pintype "passive"))
      (node (ref "U4") (pin "3") (pinfunction "VBAT_3") (pintype "passive"))
    )
    (net (code "57") (name "unconnected-(J2-KEY-Pad7)") (class "Default")
      (node (ref "J2") (pin "7") (pinfunction "KEY_7") (pintype "passive+no_connect"))
    )
    (net (code "58") (name "unconnected-(J2-TDI-Pad8)") (class "Default")
      (node (ref "J2") (pin "8") (pinfunction "TDI_8") (pintype "passive+no_connect"))
    )
    (net (code "59") (name "unconnected-(U3-NC-Pad4)") (class "Default")
      (node (ref "U3") (pin "4") (pinfunction "NC_4") (pintype "passive+no_connect"))
    )
    (net (code "60") (name "unconnected-(U6-PIO0_0{slash}FC3_SCK{slash}CTIMER0_MAT0{slash}SCT_GPI0{slash}SD1_CARD_INT_N{slash}SECURE_GPIO0_0{slash}ACMP0_A-PadL12)") (class "Default")
      (node (ref "U6") (pin "L12") (pinfunction "PIO0_0/FC3_SCK/CTIMER0_MAT0/SCT_GPI0/SD1_CARD_INT_N/SECURE_GPIO0_0/ACMP0_A_L12") (pintype "passive+no_connect"))
    )
    (net (code "61") (name "unconnected-(U6-PIO0_1{slash}FC3_CTS_SDA_SSEL0{slash}CT_INP0{slash}SCT_GPI1{slash}SD1_CLK{slash}CMP0_OUT{slash}SECURE_GPIO0_1-PadF5)") (class "Default")
      (node (ref "U6") (pin "F5") (pinfunction "PIO0_1/FC3_CTS_SDA_SSEL0/CT_INP0/SCT_GPI1/SD1_CLK/CMP0_OUT/SECURE_GPIO0_1_F5") (pintype "passive+no_connect"))
    )
    (net (code "62") (name "unconnected-(U6-PIO0_4{slash}FC4_SCK{slash}CT_INP12{slash}SCT_GPI4{slash}FC3_CTS_SDA_SSEL0{slash}SECURE_GPIO0_4-PadE7)") (class "Default")
      (node (ref "U6") (pin "E7") (pinfunction "PIO0_4/FC4_SCK/CT_INP12/SCT_GPI4/FC3_CTS_SDA_SSEL0/SECURE_GPIO0_4_E7") (pintype "passive+no_connect"))
    )
    (net (code "63") (name "unconnected-(U6-PIO0_7{slash}FC3_RTS_SCL_SSEL1{slash}SD0_CLK{slash}FC5_SCK{slash}FC1_SCK{slash}SECURE_GPIO0_7-PadG5)") (class "Default")
      (node (ref "U6") (pin "G5") (pinfunction "PIO0_7/FC3_RTS_SCL_SSEL1/SD0_CLK/FC5_SCK/FC1_SCK/SECURE_GPIO0_7_G5") (pintype "passive+no_connect"))
    )
    (net (code "64") (name "unconnected-(U6-PIO0_8{slash}FC3_SSEL3{slash}SD0_CMD{slash}FC5_RXD_SDA_MOSI_DATA{slash}SWO{slash}SECURE_GPIO0_8-PadM2)") (class "Default")
      (node (ref "U6") (pin "M2") (pinfunction "PIO0_8/FC3_SSEL3/SD0_CMD/FC5_RXD_SDA_MOSI_DATA/SWO/SECURE_GPIO0_8_M2") (pintype "passive+no_connect"))
    )
    (net (code "65") (name "unconnected-(U6-PIO0_9{slash}FC3_SSEL2{slash}SD0_POW_EN{slash}FC5_TXD_SCL_MISO_WS{slash}SECURE_GPIO0_9{slash}ACMP0_B-PadL13)") (class "Default")
      (node (ref "U6") (pin "L13") (pinfunction "PIO0_9/FC3_SSEL2/SD0_POW_EN/FC5_TXD_SCL_MISO_WS/SECURE_GPIO0_9/ACMP0_B_L13") (pintype "passive+no_connect"))
    )
    (net (code "66") (name "unconnected-(U6-PIO0_17{slash}FC4_SSEL2{slash}SD0_CARD_DET_N{slash}SCT_GPI7{slash}SCT0_OUT0{slash}SD0_CARD_INT_N{slash}PLU_IN2{slash}SECURE_GPIO0_17-PadG3)") (class "Default")
      (node (ref "U6") (pin "G3") (pinfunction "PIO0_17/FC4_SSEL2/SD0_CARD_DET_N/SCT_GPI7/SCT0_OUT0/SD0_CARD_INT_N/PLU_IN2/SECURE_GPIO0_17_G3") (pintype "passive+no_connect"))
    )
    (net (code "67") (name "unconnected-(U6-PIO0_18{slash}FC4_CTS_SDA_SSEL0{slash}SD0_WR_PRT{slash}CTIMER1_MAT0{slash}SCT0_OUT1{slash}PLU_IN3{slash}SECURE_GPIO0_18{slash}ACMP0_C-PadH9)") (class "Default")
      (node (ref "U6") (pin "H9") (pinfunction "PIO0_18/FC4_CTS_SDA_SSEL0/SD0_WR_PRT/CTIMER1_MAT0/SCT0_OUT1/PLU_IN3/SECURE_GPIO0_18/ACMP0_C_H9") (pintype "passive+no_connect"))
    )
    (net (code "68") (name "unconnected-(U6-PIO0_19{slash}FC4_RTS_SCL_SSEL1{slash}UTICK_CAP0{slash}CTIMER0_MAT2{slash}SCT0_OUT2{slash}FC7_TXD_SCL_MISO_WS{slash}PLU_IN4{slash}SECURE_GPIO0_19-PadE6)") (class "Default")
      (node (ref "U6") (pin "E6") (pinfunction "PIO0_19/FC4_RTS_SCL_SSEL1/UTICK_CAP0/CTIMER0_MAT2/SCT0_OUT2/FC7_TXD_SCL_MISO_WS/PLU_IN4/SECURE_GPIO0_19_E6") (pintype "passive+no_connect"))
    )
    (net (code "69") (name "unconnected-(U6-PIO0_21{slash}FC3_RTS_SCL_SSEL1{slash}UTICK_CAP3{slash}CTIMER3_MAT3{slash}SCT_GPI3{slash}FC7_SCK{slash}PLU_CLKIN{slash}SECURE_GPIO0_21-PadA12)") (class "Default")
      (node (ref "U6") (pin "A12") (pinfunction "PIO0_21/FC3_RTS_SCL_SSEL1/UTICK_CAP3/CTIMER3_MAT3/SCT_GPI3/FC7_SCK/PLU_CLKIN/SECURE_GPIO0_21_A12") (pintype "passive+no_connect"))
    )
    (net (code "70") (name "unconnected-(U6-PIO0_25{slash}FC0_TXD_SCL_MISO_WS{slash}SD0_D1{slash}CT_INP9{slash}SCT_GPI1{slash}SECURE_GPIO0_25-PadA11)") (class "Default")
      (node (ref "U6") (pin "A11") (pinfunction "PIO0_25/FC0_TXD_SCL_MISO_WS/SD0_D1/CT_INP9/SCT_GPI1/SECURE_GPIO0_25_A11") (pintype "passive+no_connect"))
    )
    (net (code "71") (name "unconnected-(U6-PIO1_6{slash}FC0_TXD_SCL_MISO_WS{slash}SD0_D3{slash}CTIMER2_MAT1{slash}SCT_GPI3-PadH5)") (class "Default")
      (node (ref "U6") (pin "H5") (pinfunction "PIO1_6/FC0_TXD_SCL_MISO_WS/SD0_D3/CTIMER2_MAT1/SCT_GPI3_H5") (pintype "passive+no_connect"))
    )
    (net (code "72") (name "unconnected-(U6-PIO1_7{slash}FC0_RTS_SCL_SSEL1{slash}SD0_D1{slash}CTIMER2_MAT2{slash}SCT_GPI4-PadJ5)") (class "Default")
      (node (ref "U6") (pin "J5") (pinfunction "PIO1_7/FC0_RTS_SCL_SSEL1/SD0_D1/CTIMER2_MAT2/SCT_GPI4_J5") (pintype "passive+no_connect"))
    )
    (net (code "73") (name "unconnected-(U6-PIO1_8{slash}FC0_CTS_SDA_SSEL0{slash}SD0_CLK{slash}SCT0_OUT1{slash}FC4_SSEL2{slash}ADC0_4-PadA6)") (class "Default")
      (node (ref "U6") (pin "A6") (pinfunction "PIO1_8/FC0_CTS_SDA_SSEL0/SD0_CLK/SCT0_OUT1/FC4_SSEL2/ADC0_4_A6") (pintype "passive+no_connect"))
    )
    (net (code "74") (name "unconnected-(U6-PIO1_10{slash}FC1_RXD_SDA_MOSI_DATA{slash}CTIMER1_MAT0{slash}SCT0_OUT3-PadJ7)") (class "Default")
      (node (ref "U6") (pin "J7") (pinfunction "PIO1_10/FC1_RXD_SDA_MOSI_DATA/CTIMER1_MAT0/SCT0_OUT3_J7") (pintype "passive+no_connect"))
    )
    (net (code "75") (name "unconnected-(U6-PIO1_11{slash}FC1_TXD_SCL_MISO_WS{slash}CT_INP5{slash}USB0_VBUS-PadG6)") (class "Default")
      (node (ref "U6") (pin "G6") (pinfunction "PIO1_11/FC1_TXD_SCL_MISO_WS/CT_INP5/USB0_VBUS_G6") (pintype "passive+no_connect"))
    )
    (net (code "76") (name "unconnected-(U6-PIO1_13{slash}FC6_RXD_SDA_MOSI_DATA{slash}CT_INP6{slash}USB0_OVERCURRENTN{slash}USB0_FRAME{slash}SD0_CARD_DET_N-PadB3)") (class "Default")
      (node (ref "U6") (pin "B3") (pinfunction "PIO1_13/FC6_RXD_SDA_MOSI_DATA/CT_INP6/USB0_OVERCURRENTN/USB0_FRAME/SD0_CARD_DET_N_B3") (pintype "passive+no_connect"))
    )
    (net (code "77") (name "unconnected-(U6-PIO1_14{slash}UTICK_CAP2{slash}CTIMER1_MAT2{slash}FC5_CTS_SDA_SSEL0{slash}USB0_LEDN{slash}SD1_CMD{slash}ACMP0_D-PadL7)") (class "Default")
      (node (ref "U6") (pin "L7") (pinfunction "PIO1_14/UTICK_CAP2/CTIMER1_MAT2/FC5_CTS_SDA_SSEL0/USB0_LEDN/SD1_CMD/ACMP0_D_L7") (pintype "passive+no_connect"))
    )
    (net (code "78") (name "unconnected-(U6-PIO1_15{slash}UTICK_CAP3{slash}CT_INP7{slash}FC5_RTS_SCL_SSEL1{slash}FC4_RTS_SCL_SSEL1{slash}SD1_D2-PadB6)") (class "Default")
      (node (ref "U6") (pin "B6") (pinfunction "PIO1_15/UTICK_CAP3/CT_INP7/FC5_RTS_SCL_SSEL1/FC4_RTS_SCL_SSEL1/SD1_D2_B6") (pintype "passive+no_connect"))
    )
    (net (code "79") (name "unconnected-(U6-PIO1_16{slash}FC6_TXD_SCL_MISO_WS{slash}CTIMER1_MAT3{slash}SD0_CMD-PadC7)") (class "Default")
      (node (ref "U6") (pin "C7") (pinfunction "PIO1_16/FC6_TXD_SCL_MISO_WS/CTIMER1_MAT3/SD0_CMD_C7") (pintype "passive+no_connect"))
    )
    (net (code "80") (name "unconnected-(U6-PIO1_17{slash}FC6_RTS_SCL_SSEL1{slash}SCT0_OUT4{slash}SD1_CARD_INT_N{slash}SD1_CARD_DET_N-PadJ9)") (class "Default")
      (node (ref "U6") (pin "J9") (pinfunction "PIO1_17/FC6_RTS_SCL_SSEL1/SCT0_OUT4/SD1_CARD_INT_N/SD1_CARD_DET_N_J9") (pintype "passive+no_connect"))
    )
    (net (code "81") (name "unconnected-(U6-PIO1_18{slash}SD1_POW_EN{slash}SCT0_OUT5{slash}PLU_OUT0-PadG9)") (class "Default")
      (node (ref "U6") (pin "G9") (pinfunction "PIO1_18/SD1_POW_EN/SCT0_OUT5/PLU_OUT0_G9") (pintype "passive+no_connect"))
    )
    (net (code "82") (name "unconnected-(U6-PIO1_20{slash}FC7_RTS_SCL_SSEL1{slash}CT_INP14{slash}FC4_TXD_SCL_MISO_WS{slash}PLU_OUT2-PadC2)") (class "Default")
      (node (ref "U6") (pin "C2") (pinfunction "PIO1_20/FC7_RTS_SCL_SSEL1/CT_INP14/FC4_TXD_SCL_MISO_WS/PLU_OUT2_C2") (pintype "passive+no_connect"))
    )
    (net (code "83") (name "unconnected-(U6-PIO1_21{slash}FC7_CTS_SDA_SSEL0{slash}CTIMER3_MAT2{slash}FC4_RXD_SDA_MOSI_DATA{slash}PLU_OUT3-PadM7)") (class "Default")
      (node (ref "U6") (pin "M7") (pinfunction "PIO1_21/FC7_CTS_SDA_SSEL0/CTIMER3_MAT2/FC4_RXD_SDA_MOSI_DATA/PLU_OUT3_M7") (pintype "passive+no_connect"))
    )
    (net (code "84") (name "unconnected-(U6-PIO1_23{slash}FC2_SCK{slash}SCT0_OUT0{slash}SD1_D3{slash}FC3_SSEL2{slash}PLU_OUT5-PadJ8)") (class "Default")
      (node (ref "U6") (pin "J8") (pinfunction "PIO1_23/FC2_SCK/SCT0_OUT0/SD1_D3/FC3_SSEL2/PLU_OUT5_J8") (pintype "passive+no_connect"))
    )
    (net (code "85") (name "unconnected-(U6-PIO1_24{slash}FC2_RXD_SDA_MOSI_DATA{slash}SCT0_OUT1{slash}SD1_D1{slash}FC3_SSEL3{slash}PLU_OUT6-PadF6)") (class "Default")
      (node (ref "U6") (pin "F6") (pinfunction "PIO1_24/FC2_RXD_SDA_MOSI_DATA/SCT0_OUT1/SD1_D1/FC3_SSEL3/PLU_OUT6_F6") (pintype "passive+no_connect"))
    )
    (net (code "86") (name "unconnected-(U6-PIO1_25{slash}FC2_TXD_SCL_MISO_WS{slash}SCT0_OUT2{slash}SD1_D0{slash}UTICK_CAP0{slash}PLU_CLKIN-PadB8)") (class "Default")
      (node (ref "U6") (pin "B8") (pinfunction "PIO1_25/FC2_TXD_SCL_MISO_WS/SCT0_OUT2/SD1_D0/UTICK_CAP0/PLU_CLKIN_B8") (pintype "passive+no_connect"))
    )
    (net (code "87") (name "unconnected-(U6-PIO1_27{slash}FC2_RTS_SCL_SSEL1{slash}SD0_D4{slash}CTIMER0_MAT3{slash}CLKOUT{slash}PLU_IN4-PadE8)") (class "Default")
      (node (ref "U6") (pin "E8") (pinfunction "PIO1_27/FC2_RTS_SCL_SSEL1/SD0_D4/CTIMER0_MAT3/CLKOUT/PLU_IN4_E8") (pintype "passive+no_connect"))
    )
    (net (code "88") (name "unconnected-(U6-PIO1_29{slash}FC7_RXD_SDA_MOSI_DATA{slash}SD0_D6{slash}SCT_GPI6{slash}USB1_PORTPWRN{slash}USB1_FRAME{slash}PLU_IN2-PadG8)") (class "Default")
      (node (ref "U6") (pin "G8") (pinfunction "PIO1_29/FC7_RXD_SDA_MOSI_DATA/SD0_D6/SCT_GPI6/USB1_PORTPWRN/USB1_FRAME/PLU_IN2_G8") (pintype "passive+no_connect"))
    )
    (net (code "89") (name "unconnected-(U6-PIO1_30{slash}FC7_TXD_SCL_MISO_WS{slash}SD0_D7{slash}SCT_GPI7{slash}USB1_OVERCURRENTN{slash}USB1_LEDN{slash}PLU_IN1-PadF9)") (class "Default")
      (node (ref "U6") (pin "F9") (pinfunction "PIO1_30/FC7_TXD_SCL_MISO_WS/SD0_D7/SCT_GPI7/USB1_OVERCURRENTN/USB1_LEDN/PLU_IN1_F9") (pintype "passive+no_connect"))
    )
    (net (code "90") (name "unconnected-(U6-PIO1_31{slash}MCLK{slash}SD1_CLK{slash}CTIMER0_MAT2{slash}SCT0_OUT6{slash}PLU_IN0-PadH6)") (class "Default")
      (node (ref "U6") (pin "H6") (pinfunction "PIO1_31/MCLK/SD1_CLK/CTIMER0_MAT2/SCT0_OUT6/PLU_IN0_H6") (pintype "passive+no_connect"))
    )
    (net (code "91") (name "unconnected-(U6-USB0_DM-PadA1)") (class "Default")
      (node (ref "U6") (pin "A1") (pinfunction "USB0_DM_A1") (pintype "passive+no_connect"))
    )
    (net (code "92") (name "unconnected-(U6-USB0_DP-PadA2)") (class "Default")
      (node (ref "U6") (pin "A2") (pinfunction "USB0_DP_A2") (pintype "passive+no_connect"))
    )
    (net (code "93") (name "unconnected-(U6-XTAL32K_N-PadJ12)") (class "Default")
      (node (ref "U6") (pin "J12") (pinfunction "XTAL32K_N_J12") (pintype "passive+no_connect"))
    )
    (net (code "94") (name "unconnected-(U6-XTAL32K_P-PadJ13)") (class "Default")
      (node (ref "U6") (pin "J13") (pinfunction "XTAL32K_P_J13") (pintype "passive+no_connect"))
    )
    (net (code "95") (name "unconnected-(U10-CLK-PadM6)") (class "Default")
      (node (ref "U10") (pin "M6") (pinfunction "CLK_M6") (pintype "passive"))
    )
    (net (code "96") (name "unconnected-(U10-CMD-PadM5)") (class "Default")
      (node (ref "U10") (pin "M5") (pinfunction "CMD_M5") (pintype "passive"))
    )
    (net (code "97") (name "unconnected-(U10-DAT0-PadA3)") (class "Default")
      (node (ref "U10") (pin "A3") (pinfunction "DAT0_A3") (pintype "passive"))
    )
    (net (code "98") (name "unconnected-(U10-DAT1-PadA4)") (class "Default")
      (node (ref "U10") (pin "A4") (pinfunction "DAT1_A4") (pintype "passive"))
    )
    (net (code "99") (name "unconnected-(U10-DAT2-PadA5)") (class "Default")
      (node (ref "U10") (pin "A5") (pinfunction "DAT2_A5") (pintype "passive"))
    )
    (net (code "100") (name "unconnected-(U10-DAT3-PadB2)") (class "Default")
      (node (ref "U10") (pin "B2") (pinfunction "DAT3_B2") (pintype "passive"))
    )
    (net (code "101") (name "unconnected-(U10-DAT4-PadB3)") (class "Default")
      (node (ref "U10") (pin "B3") (pinfunction "DAT4_B3") (pintype "passive"))
    )
    (net (code "102") (name "unconnected-(U10-DAT5-PadB4)") (class "Default")
      (node (ref "U10") (pin "B4") (pinfunction "DAT5_B4") (pintype "passive"))
    )
    (net (code "103") (name "unconnected-(U10-DAT6-PadB5)") (class "Default")
      (node (ref "U10") (pin "B5") (pinfunction "DAT6_B5") (pintype "passive"))
    )
    (net (code "104") (name "unconnected-(U10-DAT7-PadB6)") (class "Default")
      (node (ref "U10") (pin "B6") (pinfunction "DAT7_B6") (pintype "passive"))
    )
    (net (code "105") (name "unconnected-(U10-RCLK{slash}DS-PadH5)") (class "Default")
      (node (ref "U10") (pin "H5") (pinfunction "RCLK/DS_H5") (pintype "passive"))
    )
    (net (code "106") (name "unconnected-(U10-RFU-PadA7)") (class "Default")
      (node (ref "U10") (pin "A7") (pinfunction "RFU_A7") (pintype "passive"))
    )
    (net (code "107") (name "unconnected-(U10-RFU-PadE5)") (class "Default")
      (node (ref "U10") (pin "E5") (pinfunction "RFU_E5") (pintype "passive"))
    )
    (net (code "108") (name "unconnected-(U10-RFU-PadK6)") (class "Default")
      (node (ref "U10") (pin "K6") (pinfunction "RFU_K6") (pintype "passive"))
    )
    (net (code "109") (name "unconnected-(U10-RFU-PadK7)") (class "Default")
      (node (ref "U10") (pin "K7") (pinfunction "RFU_K7") (pintype "passive"))
    )
    (net (code "110") (name "unconnected-(U10-RST-PadK5)") (class "Default")
      (node (ref "U10") (pin "K5") (pinfunction "RST_K5") (pintype "passive"))
    )
    (net (code "111") (name "unconnected-(U10-VCC-PadE6)") (class "Default")
      (node (ref "U10") (pin "E6") (pinfunction "VCC_E6") (pintype "passive"))
    )
    (net (code "112") (name "unconnected-(U10-VCC-PadF5)") (class "Default")
      (node (ref "U10") (pin "F5") (pinfunction "VCC_F5") (pintype "passive"))
    )
    (net (code "113") (name "unconnected-(U10-VCC-PadJ10)") (class "Default")
      (node (ref "U10") (pin "J10") (pinfunction "VCC_J10") (pintype "passive"))
    )
    (net (code "114") (name "unconnected-(U10-VCC-PadK9)") (class "Default")
      (node (ref "U10") (pin "K9") (pinfunction "VCC_K9") (pintype "passive"))
    )
    (net (code "115") (name "unconnected-(U10-VCCQ-PadC6)") (class "Default")
      (node (ref "U10") (pin "C6") (pinfunction "VCCQ_C6") (pintype "passive"))
    )
    (net (code "116") (name "unconnected-(U10-VCCQ-PadM4)") (class "Default")
      (node (ref "U10") (pin "M4") (pinfunction "VCCQ_M4") (pintype "passive"))
    )
    (net (code "117") (name "unconnected-(U10-VCCQ-PadN4)") (class "Default")
      (node (ref "U10") (pin "N4") (pinfunction "VCCQ_N4") (pintype "passive"))
    )
    (net (code "118") (name "unconnected-(U10-VCCQ-PadP3)") (class "Default")
      (node (ref "U10") (pin "P3") (pinfunction "VCCQ_P3") (pintype "passive"))
    )
    (net (code "119") (name "unconnected-(U10-VCCQ-PadP5)") (class "Default")
      (node (ref "U10") (pin "P5") (pinfunction "VCCQ_P5") (pintype "passive"))
    )
    (net (code "120") (name "unconnected-(U10-VDDI-PadC2)") (class "Default")
      (node (ref "U10") (pin "C2") (pinfunction "VDDI_C2") (pintype "passive"))
    )
    (net (code "121") (name "unconnected-(U10-VSF-PadE8)") (class "Default")
      (node (ref "U10") (pin "E8") (pinfunction "VSF_E8") (pintype "passive"))
    )
    (net (code "122") (name "unconnected-(U10-VSF-PadE9)") (class "Default")
      (node (ref "U10") (pin "E9") (pinfunction "VSF_E9") (pintype "passive"))
    )
    (net (code "123") (name "unconnected-(U10-VSF-PadE10)") (class "Default")
      (node (ref "U10") (pin "E10") (pinfunction "VSF_E10") (pintype "passive"))
    )
    (net (code "124") (name "unconnected-(U10-VSF-PadF10)") (class "Default")
      (node (ref "U10") (pin "F10") (pinfunction "VSF_F10") (pintype "passive"))
    )
    (net (code "125") (name "unconnected-(U10-VSF-PadG10)") (class "Default")
      (node (ref "U10") (pin "G10") (pinfunction "VSF_G10") (pintype "passive"))
    )
    (net (code "126") (name "unconnected-(U10-VSF-PadK10)") (class "Default")
      (node (ref "U10") (pin "K10") (pinfunction "VSF_K10") (pintype "passive"))
    )
    (net (code "127") (name "unconnected-(U10-VSF-PadP10)") (class "Default")
      (node (ref "U10") (pin "P10") (pinfunction "VSF_P10") (pintype "passive"))
    )
    (net (code "128") (name "unconnected-(U10-VSS-PadA6)") (class "Default")
      (node (ref "U10") (pin "A6") (pinfunction "VSS_A6") (pintype "passive"))
    )
    (net (code "129") (name "unconnected-(U10-VSS-PadE7)") (class "Default")
      (node (ref "U10") (pin "E7") (pinfunction "VSS_E7") (pintype "passive"))
    )
    (net (code "130") (name "unconnected-(U10-VSS-PadG5)") (class "Default")
      (node (ref "U10") (pin "G5") (pinfunction "VSS_G5") (pintype "passive"))
    )
    (net (code "131") (name "unconnected-(U10-VSS-PadH10)") (class "Default")
      (node (ref "U10") (pin "H10") (pinfunction "VSS_H10") (pintype "passive"))
    )
    (net (code "132") (name "unconnected-(U10-VSS-PadJ5)") (class "Default")
      (node (ref "U10") (pin "J5") (pinfunction "VSS_J5") (pintype "passive"))
    )
    (net (code "133") (name "unconnected-(U10-VSS-PadK8)") (class "Default")
      (node (ref "U10") (pin "K8") (pinfunction "VSS_K8") (pintype "passive"))
    )
    (net (code "134") (name "unconnected-(U10-VSSQ-PadC4)") (class "Default")
      (node (ref "U10") (pin "C4") (pinfunction "VSSQ_C4") (pintype "passive"))
    )
    (net (code "135") (name "unconnected-(U10-VSSQ-PadN2)") (class "Default")
      (node (ref "U10") (pin "N2") (pinfunction "VSSQ_N2") (pintype "passive"))
    )
    (net (code "136") (name "unconnected-(U10-VSSQ-PadN5)") (class "Default")
      (node (ref "U10") (pin "N5") (pinfunction "VSSQ_N5") (pintype "passive"))
    )
    (net (code "137") (name "unconnected-(U10-VSSQ-PadP4)") (class "Default")
      (node (ref "U10") (pin "P4") (pinfunction "VSSQ_P4") (pintype "passive"))
    )
    (net (code "138") (name "unconnected-(U10-VSSQ-PadP6)") (class "Default")
      (node (ref "U10") (pin "P6") (pinfunction "VSSQ_P6") (pintype "passive"))
    )
  )
)
